# LED_Indicator.net
KiCad netlist of a schematic drawn in Altium Designer
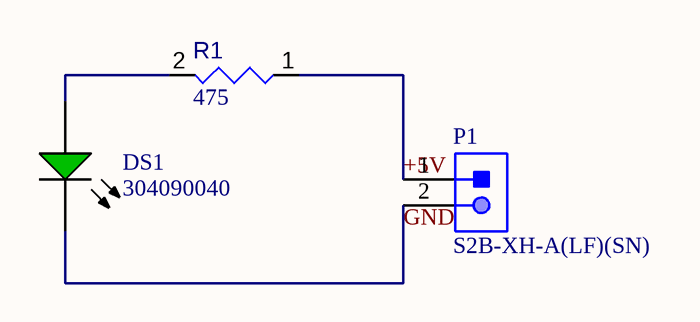
[diagram p0: LED_Indicator.SchDoc]

(export (version "E")
  (design (tool "Eeschema 10.0.6"))
  (components
    (comp (ref "DS1")
      (value "304090040")
      (footprint "LED-2P-2.28-3MM")
      (description "Green LED, 80 mW, 20 mA, -25 to 85 degC, 2-Pin THD")
      (fields (field (name "MANUFACTURER") "Shenzhen CGX"))
      (libsource (lib "Yuvan Bala") (part "LED-GREEN-AK-2"))
    )
    (comp (ref "P1")
      (value "S2B-XH-A(LF)(SN)")
      (footprint "JST-S2B-XH-A(LF)(SN)_V")
      (fields (field (name "MANUFACTURER") "JST"))
      (libsource (lib "Yuvan Bala") (part "CN-1P-M-R2"))
    )
    (comp (ref "R1")
      (value "475")
      (footprint "RESA60-630X240")
      (description "Axial Resistor, 475 Ohm, +/- 1%, 0.25 W, -55 to 155 degC, 2-Pin THD, RoHS, Bulk")
      (fields (field (name "MANUFACTURER") "Yageo") (field (name "TOLERANCE") "1%"))
      (libsource (lib "Yuvan Bala") (part "RES-2"))
    )
  )
  (nets
    (net (code "1") (name "/+5V") (class "Default")
      (node (ref "P1") (pin "1") (pinfunction "1_1") (pintype "passive"))
      (node (ref "R1") (pin "1") (pinfunction "1_1") (pintype "passive"))
    )
    (net (code "2") (name "/GND") (class "Default")
      (node (ref "DS1") (pin "2") (pinfunction "K_2") (pintype "passive"))
      (node (ref "P1") (pin "2") (pinfunction "2_2") (pintype "passive"))
    )
    (net (code "3") (name "Net-(DS1-A)") (class "Default")
      (node (ref "DS1") (pin "1") (pinfunction "A_1") (pintype "passive"))
      (node (ref "R1") (pin "2") (pinfunction "2_2") (pintype "passive"))
    )
  )
)
